# atmega32u4-breakout-v3.net
KiCad netlist of a schematic drawn in EAGLE
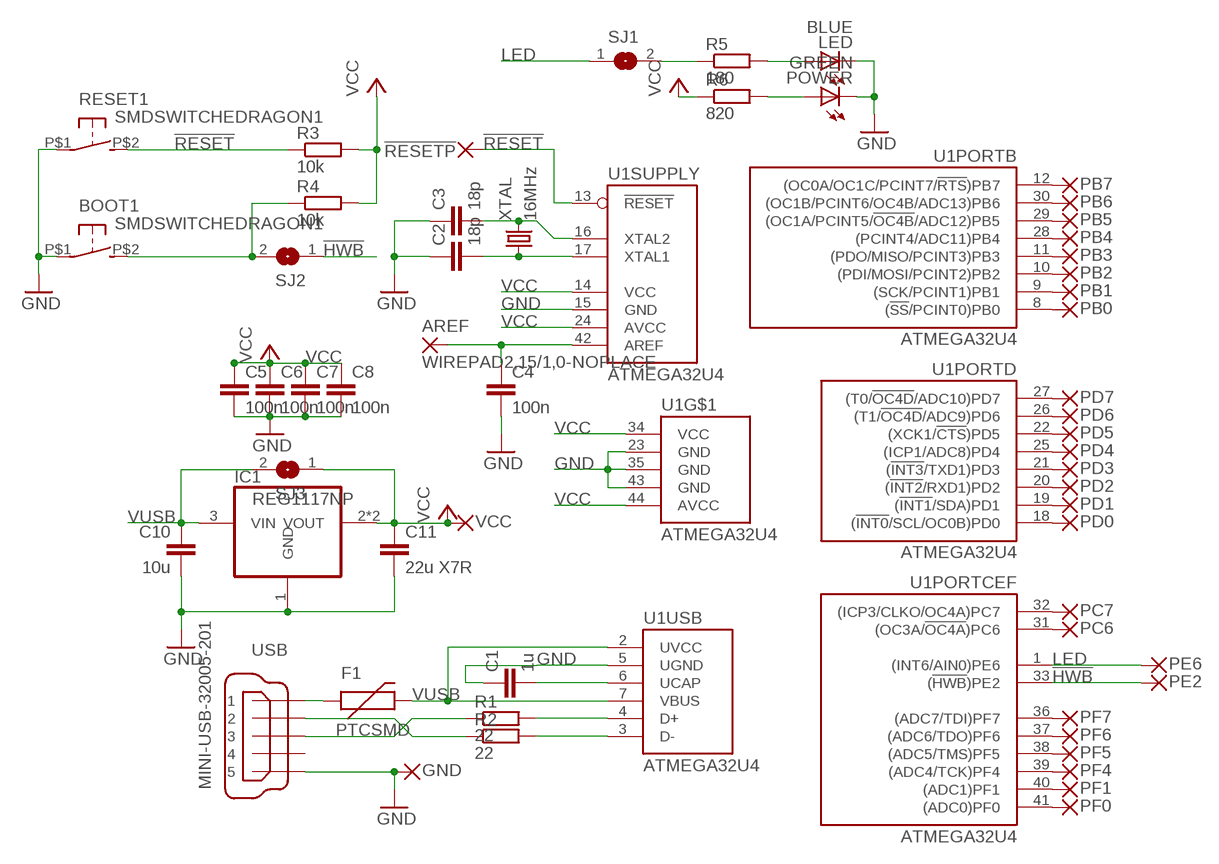
[diagram p0: schematic, sheet 1]

(export (version "E")
  (design (tool "Eeschema 10.0.6"))
  (components
    (comp (ref "!RESETP")
      (value "WIREPAD2,15/1,0-NOPLACE")
      (footprint "eagle-import:2,15_1,0-NOPLACE")
      (libsource (lib "eagle-import") (part "WIREPAD2,15/1,0-NOPLACE"))
    )
    (comp (ref "AREF")
      (value "WIREPAD2,15/1,0-NOPLACE")
      (footprint "eagle-import:2,15_1,0-NOPLACE")
      (libsource (lib "eagle-import") (part "WIREPAD2,15/1,0-NOPLACE"))
    )
    (comp (ref "BOOT1")
      (value "SMDSWITCHEDRAGON1")
      (footprint "eagle-import:EDRAGON1")
      (libsource (lib "eagle-import") (part "SMDSWITCHEDRAGON1"))
    )
    (comp (ref "C1")
      (value "1u")
      (footprint "eagle-import:C0603")
      (libsource (lib "eagle-import") (part "C-EUC0603"))
    )
    (comp (ref "C2")
      (value "18p")
      (footprint "eagle-import:C0603")
      (libsource (lib "eagle-import") (part "C-EUC0603"))
    )
    (comp (ref "C3")
      (value "18p")
      (footprint "eagle-import:C0603")
      (libsource (lib "eagle-import") (part "C-EUC0603"))
    )
    (comp (ref "C4")
      (value "100n")
      (footprint "eagle-import:C0603")
      (libsource (lib "eagle-import") (part "C-EUC0603"))
    )
    (comp (ref "C5")
      (value "100n")
      (footprint "eagle-import:C0603")
      (libsource (lib "eagle-import") (part "C-EUC0603"))
    )
    (comp (ref "C6")
      (value "100n")
      (footprint "eagle-import:C0603")
      (libsource (lib "eagle-import") (part "C-EUC0603"))
    )
    (comp (ref "C7")
      (value "100n")
      (footprint "eagle-import:C0603")
      (libsource (lib "eagle-import") (part "C-EUC0603"))
    )
    (comp (ref "C8")
      (value "100n")
      (footprint "eagle-import:C0603")
      (libsource (lib "eagle-import") (part "C-EUC0603"))
    )
    (comp (ref "C10")
      (value "10u")
      (footprint "eagle-import:C0805K")
      (libsource (lib "eagle-import") (part "C-EUC0805K"))
    )
    (comp (ref "C11")
      (value "22u X7R")
      (footprint "eagle-import:C1206K")
      (libsource (lib "eagle-import") (part "C-EUC1206K"))
    )
    (comp (ref "F1")
      (value "PTCSMD")
      (footprint "eagle-import:PTC-1206")
      (libsource (lib "eagle-import") (part "PTCSMD"))
    )
    (comp (ref "GND")
      (value "WIREPAD2,15/1,0-NOPLACE")
      (footprint "eagle-import:2,15_1,0-NOPLACE")
      (libsource (lib "eagle-import") (part "WIREPAD2,15/1,0-NOPLACE"))
    )
    (comp (ref "IC1")
      (value "REG1117NP")
      (footprint "eagle-import:SOT223-NP")
      (libsource (lib "eagle-import") (part "REG1117NP"))
    )
    (comp (ref "LED")
      (value "BLUE")
      (footprint "eagle-import:CHIPLED_0805")
      (libsource (lib "eagle-import") (part "LEDCHIPLED_0805"))
    )
    (comp (ref "PB0")
      (value "WIREPAD2,15/1,0-NOPLACE")
      (footprint "eagle-import:2,15_1,0-NOPLACE")
      (libsource (lib "eagle-import") (part "WIREPAD2,15/1,0-NOPLACE"))
    )
    (comp (ref "PB1")
      (value "WIREPAD2,15/1,0-NOPLACE")
      (footprint "eagle-import:2,15_1,0-NOPLACE")
      (libsource (lib "eagle-import") (part "WIREPAD2,15/1,0-NOPLACE"))
    )
    (comp (ref "PB2")
      (value "WIREPAD2,15/1,0-NOPLACE")
      (footprint "eagle-import:2,15_1,0-NOPLACE")
      (libsource (lib "eagle-import") (part "WIREPAD2,15/1,0-NOPLACE"))
    )
    (comp (ref "PB3")
      (value "WIREPAD2,15/1,0-NOPLACE")
      (footprint "eagle-import:2,15_1,0-NOPLACE")
      (libsource (lib "eagle-import") (part "WIREPAD2,15/1,0-NOPLACE"))
    )
    (comp (ref "PB4")
      (value "WIREPAD2,15/1,0-NOPLACE")
      (footprint "eagle-import:2,15_1,0-NOPLACE")
      (libsource (lib "eagle-import") (part "WIREPAD2,15/1,0-NOPLACE"))
    )
    (comp (ref "PB5")
      (value "WIREPAD2,15/1,0-NOPLACE")
      (footprint "eagle-import:2,15_1,0-NOPLACE")
      (libsource (lib "eagle-import") (part "WIREPAD2,15/1,0-NOPLACE"))
    )
    (comp (ref "PB6")
      (value "WIREPAD2,15/1,0-NOPLACE")
      (footprint "eagle-import:2,15_1,0-NOPLACE")
      (libsource (lib "eagle-import") (part "WIREPAD2,15/1,0-NOPLACE"))
    )
    (comp (ref "PB7")
      (value "WIREPAD2,15/1,0-NOPLACE")
      (footprint "eagle-import:2,15_1,0-NOPLACE")
      (libsource (lib "eagle-import") (part "WIREPAD2,15/1,0-NOPLACE"))
    )
    (comp (ref "PC6")
      (value "WIREPAD2,15/1,0-NOPLACE")
      (footprint "eagle-import:2,15_1,0-NOPLACE")
      (libsource (lib "eagle-import") (part "WIREPAD2,15/1,0-NOPLACE"))
    )
    (comp (ref "PC7")
      (value "WIREPAD2,15/1,0-NOPLACE")
      (footprint "eagle-import:2,15_1,0-NOPLACE")
      (libsource (lib "eagle-import") (part "WIREPAD2,15/1,0-NOPLACE"))
    )
    (comp (ref "PD0")
      (value "WIREPAD2,15/1,0-NOPLACE")
      (footprint "eagle-import:2,15_1,0-NOPLACE")
      (libsource (lib "eagle-import") (part "WIREPAD2,15/1,0-NOPLACE"))
    )
    (comp (ref "PD1")
      (value "WIREPAD2,15/1,0-NOPLACE")
      (footprint "eagle-import:2,15_1,0-NOPLACE")
      (libsource (lib "eagle-import") (part "WIREPAD2,15/1,0-NOPLACE"))
    )
    (comp (ref "PD2")
      (value "WIREPAD2,15/1,0-NOPLACE")
      (footprint "eagle-import:2,15_1,0-NOPLACE")
      (libsource (lib "eagle-import") (part "WIREPAD2,15/1,0-NOPLACE"))
    )
    (comp (ref "PD3")
      (value "WIREPAD2,15/1,0-NOPLACE")
      (footprint "eagle-import:2,15_1,0-NOPLACE")
      (libsource (lib "eagle-import") (part "WIREPAD2,15/1,0-NOPLACE"))
    )
    (comp (ref "PD4")
      (value "WIREPAD2,15/1,0-NOPLACE")
      (footprint "eagle-import:2,15_1,0-NOPLACE")
      (libsource (lib "eagle-import") (part "WIREPAD2,15/1,0-NOPLACE"))
    )
    (comp (ref "PD5")
      (value "WIREPAD2,15/1,0-NOPLACE")
      (footprint "eagle-import:2,15_1,0-NOPLACE")
      (libsource (lib "eagle-import") (part "WIREPAD2,15/1,0-NOPLACE"))
    )
    (comp (ref "PD6")
      (value "WIREPAD2,15/1,0-NOPLACE")
      (footprint "eagle-import:2,15_1,0-NOPLACE")
      (libsource (lib "eagle-import") (part "WIREPAD2,15/1,0-NOPLACE"))
    )
    (comp (ref "PD7")
      (value "WIREPAD2,15/1,0-NOPLACE")
      (footprint "eagle-import:2,15_1,0-NOPLACE")
      (libsource (lib "eagle-import") (part "WIREPAD2,15/1,0-NOPLACE"))
    )
    (comp (ref "PE2")
      (value "WIREPAD2,15/1,0-NOPLACE")
      (footprint "eagle-import:2,15_1,0-NOPLACE")
      (libsource (lib "eagle-import") (part "WIREPAD2,15/1,0-NOPLACE"))
    )
    (comp (ref "PE6")
      (value "WIREPAD2,15/1,0-NOPLACE")
      (footprint "eagle-import:2,15_1,0-NOPLACE")
      (libsource (lib "eagle-import") (part "WIREPAD2,15/1,0-NOPLACE"))
    )
    (comp (ref "PF0")
      (value "WIREPAD2,15/1,0-NOPLACE")
      (footprint "eagle-import:2,15_1,0-NOPLACE")
      (libsource (lib "eagle-import") (part "WIREPAD2,15/1,0-NOPLACE"))
    )
    (comp (ref "PF1")
      (value "WIREPAD2,15/1,0-NOPLACE")
      (footprint "eagle-import:2,15_1,0-NOPLACE")
      (libsource (lib "eagle-import") (part "WIREPAD2,15/1,0-NOPLACE"))
    )
    (comp (ref "PF4")
      (value "WIREPAD2,15/1,0-NOPLACE")
      (footprint "eagle-import:2,15_1,0-NOPLACE")
      (libsource (lib "eagle-import") (part "WIREPAD2,15/1,0-NOPLACE"))
    )
    (comp (ref "PF5")
      (value "WIREPAD2,15/1,0-NOPLACE")
      (footprint "eagle-import:2,15_1,0-NOPLACE")
      (libsource (lib "eagle-import") (part "WIREPAD2,15/1,0-NOPLACE"))
    )
    (comp (ref "PF6")
      (value "WIREPAD2,15/1,0-NOPLACE")
      (footprint "eagle-import:2,15_1,0-NOPLACE")
      (libsource (lib "eagle-import") (part "WIREPAD2,15/1,0-NOPLACE"))
    )
    (comp (ref "PF7")
      (value "WIREPAD2,15/1,0-NOPLACE")
      (footprint "eagle-import:2,15_1,0-NOPLACE")
      (libsource (lib "eagle-import") (part "WIREPAD2,15/1,0-NOPLACE"))
    )
    (comp (ref "POWER")
      (value "GREEN")
      (footprint "eagle-import:CHIPLED_0805")
      (libsource (lib "eagle-import") (part "LEDCHIPLED_0805"))
    )
    (comp (ref "R1")
      (value "22")
      (footprint "eagle-import:R0603")
      (libsource (lib "eagle-import") (part "R-EU_R0603"))
    )
    (comp (ref "R2")
      (value "22")
      (footprint "eagle-import:R0603")
      (libsource (lib "eagle-import") (part "R-EU_R0603"))
    )
    (comp (ref "R3")
      (value "10k")
      (footprint "eagle-import:R0603")
      (libsource (lib "eagle-import") (part "R-EU_R0603"))
    )
    (comp (ref "R4")
      (value "10k")
      (footprint "eagle-import:R0603")
      (libsource (lib "eagle-import") (part "R-EU_R0603"))
    )
    (comp (ref "R5")
      (value "180")
      (footprint "eagle-import:R0603")
      (libsource (lib "eagle-import") (part "R-EU_R0603"))
    )
    (comp (ref "R6")
      (value "820")
      (footprint "eagle-import:R0603")
      (libsource (lib "eagle-import") (part "R-EU_R0603"))
    )
    (comp (ref "RESET1")
      (value "SMDSWITCHEDRAGON1")
      (footprint "eagle-import:EDRAGON1")
      (libsource (lib "eagle-import") (part "SMDSWITCHEDRAGON1"))
    )
    (comp (ref "SJ1") (value "SJ") (footprint "eagle-import:SJ") (libsource (lib "eagle-import") (part "SJ")))
    (comp (ref "SJ2") (value "SJ") (footprint "eagle-import:SJ") (libsource (lib "eagle-import") (part "SJ")))
    (comp (ref "SJ3")
      (value "SJNP")
      (footprint "eagle-import:SJNP")
      (libsource (lib "eagle-import") (part "SJNP"))
    )
    (comp (ref "U1")
      (value "ATMEGA32U4")
      (footprint "eagle-import:TQFP44")
      (libsource (lib "eagle-import") (part "ATMEGAXU4TQFP44"))
    )
    (comp (ref "USB")
      (value "MINI-USB-32005-201")
      (footprint "eagle-import:32005-201")
      (libsource (lib "eagle-import") (part "MINI-USB-32005-201"))
    )
    (comp (ref "VCC")
      (value "WIREPAD2,15/1,0-NOPLACE")
      (footprint "eagle-import:2,15_1,0-NOPLACE")
      (libsource (lib "eagle-import") (part "WIREPAD2,15/1,0-NOPLACE"))
    )
    (comp (ref "XTAL")
      (value "16MHz")
      (footprint "eagle-import:ABM7")
      (libsource (lib "eagle-import") (part "CRYSTALABM7"))
    )
  )
  (nets
    (net (code "1") (name "/LED") (class "Default")
      (node (ref "PE6") (pin "1") (pinfunction "P_1") (pintype "passive"))
      (node (ref "SJ1") (pin "1") (pinfunction "1_1") (pintype "passive"))
      (node (ref "U1") (pin "1") (pinfunction "(INT6/AIN0)PE6_1") (pintype "bidirectional"))
    )
    (net (code "2") (name "/VUSB") (class "Default")
      (node (ref "C10") (pin "1") (pinfunction "1_1") (pintype "passive"))
      (node (ref "F1") (pin "2") (pinfunction "2_2") (pintype "bidirectional"))
      (node (ref "IC1") (pin "3") (pinfunction "VIN_3") (pintype "input"))
      (node (ref "SJ3") (pin "2") (pinfunction "2_2") (pintype "passive"))
      (node (ref "U1") (pin "2") (pinfunction "UVCC_2") (pintype "power_in"))
      (node (ref "U1") (pin "7") (pinfunction "VBUS_7") (pintype "power_in"))
    )
    (net (code "3") (name "/~{HWB}") (class "Default")
      (node (ref "PE2") (pin "1") (pinfunction "P_1") (pintype "passive"))
      (node (ref "SJ2") (pin "1") (pinfunction "1_1") (pintype "passive"))
      (node (ref "U1") (pin "33") (pinfunction "(~{HWB})PE2_33") (pintype "bidirectional"))
    )
    (net (code "4") (name "/~{RESET}") (class "Default")
      (node (ref "!RESETP") (pin "1") (pinfunction "P_1") (pintype "passive"))
      (node (ref "R3") (pin "1") (pinfunction "1_1") (pintype "passive"))
      (node (ref "RESET1") (pin "P$2") (pinfunction "S_P$2") (pintype "passive"))
      (node (ref "U1") (pin "13") (pinfunction "~{RESET}_13") (pintype "input"))
    )
    (net (code "5") (name "GND") (class "Default")
      (node (ref "BOOT1") (pin "P$1") (pinfunction "P_P$1") (pintype "passive"))
      (node (ref "C1") (pin "1") (pinfunction "1_1") (pintype "passive"))
      (node (ref "C10") (pin "2") (pinfunction "2_2") (pintype "passive"))
      (node (ref "C11") (pin "2") (pinfunction "2_2") (pintype "passive"))
      (node (ref "C2") (pin "1") (pinfunction "1_1") (pintype "passive"))
      (node (ref "C3") (pin "1") (pinfunction "1_1") (pintype "passive"))
      (node (ref "C4") (pin "2") (pinfunction "2_2") (pintype "passive"))
      (node (ref "C5") (pin "2") (pinfunction "2_2") (pintype "passive"))
      (node (ref "C6") (pin "2") (pinfunction "2_2") (pintype "passive"))
      (node (ref "C7") (pin "2") (pinfunction "2_2") (pintype "passive"))
      (node (ref "C8") (pin "2") (pinfunction "2_2") (pintype "passive"))
      (node (ref "GND") (pin "1") (pinfunction "P_1") (pintype "passive"))
      (node (ref "IC1") (pin "1") (pinfunction "GND_1") (pintype "power_in"))
      (node (ref "LED") (pin "C") (pinfunction "C_C") (pintype "passive"))
      (node (ref "POWER") (pin "C") (pinfunction "C_C") (pintype "passive"))
      (node (ref "RESET1") (pin "P$1") (pinfunction "P_P$1") (pintype "passive"))
      (node (ref "U1") (pin "15") (pinfunction "GND_15") (pintype "power_in"))
      (node (ref "U1") (pin "23") (pinfunction "GND_23") (pintype "power_in"))
      (node (ref "U1") (pin "35") (pinfunction "GND_35") (pintype "power_in"))
      (node (ref "U1") (pin "43") (pinfunction "GND_43") (pintype "power_in"))
      (node (ref "U1") (pin "5") (pinfunction "UGND_5") (pintype "power_in"))
      (node (ref "USB") (pin "5") (pinfunction "5_5") (pintype "passive"))
    )
    (net (code "6") (name "Net-(AREF-P)") (class "Default")
      (node (ref "AREF") (pin "1") (pinfunction "P_1") (pintype "passive"))
      (node (ref "C4") (pin "1") (pinfunction "1_1") (pintype "passive"))
      (node (ref "U1") (pin "42") (pinfunction "AREF_42") (pintype "power_in"))
    )
    (net (code "7") (name "Net-(BOOT1-S)") (class "Default")
      (node (ref "BOOT1") (pin "P$2") (pinfunction "S_P$2") (pintype "passive"))
      (node (ref "R4") (pin "1") (pinfunction "1_1") (pintype "passive"))
      (node (ref "SJ2") (pin "2") (pinfunction "2_2") (pintype "passive"))
    )
    (net (code "8") (name "Net-(F1-Pad1)") (class "Default")
      (node (ref "F1") (pin "1") (pinfunction "1_1") (pintype "bidirectional"))
      (node (ref "USB") (pin "1") (pinfunction "1_1") (pintype "passive"))
    )
    (net (code "9") (name "Net-(LED-PadA)") (class "Default")
      (node (ref "LED") (pin "A") (pinfunction "A_A") (pintype "passive"))
      (node (ref "R5") (pin "2") (pinfunction "2_2") (pintype "passive"))
    )
    (net (code "10") (name "Net-(PB0-P)") (class "Default")
      (node (ref "PB0") (pin "1") (pinfunction "P_1") (pintype "passive"))
      (node (ref "U1") (pin "8") (pinfunction "(~{SS}/PCINT0)PB0_8") (pintype "bidirectional"))
    )
    (net (code "11") (name "Net-(PB1-P)") (class "Default")
      (node (ref "PB1") (pin "1") (pinfunction "P_1") (pintype "passive"))
      (node (ref "U1") (pin "9") (pinfunction "(SCK/PCINT1)PB1_9") (pintype "bidirectional"))
    )
    (net (code "12") (name "Net-(PB2-P)") (class "Default")
      (node (ref "PB2") (pin "1") (pinfunction "P_1") (pintype "passive"))
      (node (ref "U1") (pin "10") (pinfunction "(PDI/MOSI/PCINT2)PB2_10") (pintype "bidirectional"))
    )
    (net (code "13") (name "Net-(PB3-P)") (class "Default")
      (node (ref "PB3") (pin "1") (pinfunction "P_1") (pintype "passive"))
      (node (ref "U1") (pin "11") (pinfunction "(PDO/MISO/PCINT3)PB3_11") (pintype "bidirectional"))
    )
    (net (code "14") (name "Net-(PB4-P)") (class "Default")
      (node (ref "PB4") (pin "1") (pinfunction "P_1") (pintype "passive"))
      (node (ref "U1") (pin "28") (pinfunction "(PCINT4/ADC11)PB4_28") (pintype "bidirectional"))
    )
    (net (code "15") (name "Net-(PB5-P)") (class "Default")
      (node (ref "PB5") (pin "1") (pinfunction "P_1") (pintype "passive"))
      (node (ref "U1") (pin "29") (pinfunction "(OC1A/PCINT5/~{OC4B}/ADC12)PB5_29") (pintype "bidirectional"))
    )
    (net (code "16") (name "Net-(PB6-P)") (class "Default")
      (node (ref "PB6") (pin "1") (pinfunction "P_1") (pintype "passive"))
      (node (ref "U1") (pin "30") (pinfunction "(OC1B/PCINT6/OC4B/ADC13)PB6_30") (pintype "bidirectional"))
    )
    (net (code "17") (name "Net-(PB7-P)") (class "Default")
      (node (ref "PB7") (pin "1") (pinfunction "P_1") (pintype "passive"))
      (node (ref "U1") (pin "12") (pinfunction "(OC0A/OC1C/PCINT7/~{RTS})PB7_12") (pintype "bidirectional"))
    )
    (net (code "18") (name "Net-(PC6-P)") (class "Default")
      (node (ref "PC6") (pin "1") (pinfunction "P_1") (pintype "passive"))
      (node (ref "U1") (pin "31") (pinfunction "(OC3A/~{OC4A})PC6_31") (pintype "bidirectional"))
    )
    (net (code "19") (name "Net-(PC7-P)") (class "Default")
      (node (ref "PC7") (pin "1") (pinfunction "P_1") (pintype "passive"))
      (node (ref "U1") (pin "32") (pinfunction "(ICP3/CLKO/OC4A)PC7_32") (pintype "bidirectional"))
    )
    (net (code "20") (name "Net-(PD0-P)") (class "Default")
      (node (ref "PD0") (pin "1") (pinfunction "P_1") (pintype "passive"))
      (node (ref "U1") (pin "18") (pinfunction "(~{INT0}/SCL/OC0B)PD0_18") (pintype "bidirectional"))
    )
    (net (code "21") (name "Net-(PD1-P)") (class "Default")
      (node (ref "PD1") (pin "1") (pinfunction "P_1") (pintype "passive"))
      (node (ref "U1") (pin "19") (pinfunction "(~{INT1}/SDA)PD1_19") (pintype "bidirectional"))
    )
    (net (code "22") (name "Net-(PD2-P)") (class "Default")
      (node (ref "PD2") (pin "1") (pinfunction "P_1") (pintype "passive"))
      (node (ref "U1") (pin "20") (pinfunction "(~{INT2}/RXD1)PD2_20") (pintype "bidirectional"))
    )
    (net (code "23") (name "Net-(PD3-P)") (class "Default")
      (node (ref "PD3") (pin "1") (pinfunction "P_1") (pintype "passive"))
      (node (ref "U1") (pin "21") (pinfunction "(~{INT3}/TXD1)PD3_21") (pintype "bidirectional"))
    )
    (net (code "24") (name "Net-(PD4-P)") (class "Default")
      (node (ref "PD4") (pin "1") (pinfunction "P_1") (pintype "passive"))
      (node (ref "U1") (pin "25") (pinfunction "(ICP1/ADC8)PD4_25") (pintype "bidirectional"))
    )
    (net (code "25") (name "Net-(PD5-P)") (class "Default")
      (node (ref "PD5") (pin "1") (pinfunction "P_1") (pintype "passive"))
      (node (ref "U1") (pin "22") (pinfunction "(XCK1/~{CTS})PD5_22") (pintype "bidirectional"))
    )
    (net (code "26") (name "Net-(PD6-P)") (class "Default")
      (node (ref "PD6") (pin "1") (pinfunction "P_1") (pintype "passive"))
      (node (ref "U1") (pin "26") (pinfunction "(T1/~{OC4D}/ADC9)PD6_26") (pintype "bidirectional"))
    )
    (net (code "27") (name "Net-(PD7-P)") (class "Default")
      (node (ref "PD7") (pin "1") (pinfunction "P_1") (pintype "passive"))
      (node (ref "U1") (pin "27") (pinfunction "(T0/~{OC4D}/ADC10)PD7_27") (pintype "bidirectional"))
    )
    (net (code "28") (name "Net-(PF0-P)") (class "Default")
      (node (ref "PF0") (pin "1") (pinfunction "P_1") (pintype "passive"))
      (node (ref "U1") (pin "41") (pinfunction "(ADC0)PF0_41") (pintype "bidirectional"))
    )
    (net (code "29") (name "Net-(PF1-P)") (class "Default")
      (node (ref "PF1") (pin "1") (pinfunction "P_1") (pintype "passive"))
      (node (ref "U1") (pin "40") (pinfunction "(ADC1)PF1_40") (pintype "bidirectional"))
    )
    (net (code "30") (name "Net-(PF4-P)") (class "Default")
      (node (ref "PF4") (pin "1") (pinfunction "P_1") (pintype "passive"))
      (node (ref "U1") (pin "39") (pinfunction "(ADC4/TCK)PF4_39") (pintype "bidirectional"))
    )
    (net (code "31") (name "Net-(PF5-P)") (class "Default")
      (node (ref "PF5") (pin "1") (pinfunction "P_1") (pintype "passive"))
      (node (ref "U1") (pin "38") (pinfunction "(ADC5/TMS)PF5_38") (pintype "bidirectional"))
    )
    (net (code "32") (name "Net-(PF6-P)") (class "Default")
      (node (ref "PF6") (pin "1") (pinfunction "P_1") (pintype "passive"))
      (node (ref "U1") (pin "37") (pinfunction "(ADC6/TDO)PF6_37") (pintype "bidirectional"))
    )
    (net (code "33") (name "Net-(PF7-P)") (class "Default")
      (node (ref "PF7") (pin "1") (pinfunction "P_1") (pintype "passive"))
      (node (ref "U1") (pin "36") (pinfunction "(ADC7/TDI)PF7_36") (pintype "bidirectional"))
    )
    (net (code "34") (name "Net-(POWER-PadA)") (class "Default")
      (node (ref "POWER") (pin "A") (pinfunction "A_A") (pintype "passive"))
      (node (ref "R6") (pin "2") (pinfunction "2_2") (pintype "passive"))
    )
    (net (code "35") (name "Net-(R1-Pad1)") (class "Default")
      (node (ref "R1") (pin "1") (pinfunction "1_1") (pintype "passive"))
      (node (ref "USB") (pin "3") (pinfunction "3_3") (pintype "passive"))
    )
    (net (code "36") (name "Net-(R2-Pad1)") (class "Default")
      (node (ref "R2") (pin "1") (pinfunction "1_1") (pintype "passive"))
      (node (ref "USB") (pin "2") (pinfunction "2_2") (pintype "passive"))
    )
    (net (code "37") (name "Net-(R5-Pad1)") (class "Default")
      (node (ref "R5") (pin "1") (pinfunction "1_1") (pintype "passive"))
      (node (ref "SJ1") (pin "2") (pinfunction "2_2") (pintype "passive"))
    )
    (net (code "38") (name "Net-(U1E-XTAL1)") (class "Default")
      (node (ref "C2") (pin "2") (pinfunction "2_2") (pintype "passive"))
      (node (ref "U1") (pin "17") (pinfunction "XTAL1_17") (pintype "bidirectional"))
      (node (ref "XTAL") (pin "P$1") (pinfunction "1_P$1") (pintype "passive"))
    )
    (net (code "39") (name "Net-(U1E-XTAL2)") (class "Default")
      (node (ref "C3") (pin "2") (pinfunction "2_2") (pintype "passive"))
      (node (ref "U1") (pin "16") (pinfunction "XTAL2_16") (pintype "bidirectional"))
      (node (ref "XTAL") (pin "P$2") (pinfunction "2_P$2") (pintype "passive"))
    )
    (net (code "40") (name "Net-(U1F-D+)") (class "Default")
      (node (ref "R1") (pin "2") (pinfunction "2_2") (pintype "passive"))
      (node (ref "U1") (pin "4") (pinfunction "D+_4") (pintype "bidirectional"))
    )
    (net (code "41") (name "Net-(U1F-D-)") (class "Default")
      (node (ref "R2") (pin "2") (pinfunction "2_2") (pintype "passive"))
      (node (ref "U1") (pin "3") (pinfunction "D-_3") (pintype "bidirectional"))
    )
    (net (code "42") (name "Net-(U1F-UCAP)") (class "Default")
      (node (ref "C1") (pin "2") (pinfunction "2_2") (pintype "passive"))
      (node (ref "U1") (pin "6") (pinfunction "UCAP_6") (pintype "power_in"))
    )
    (net (code "43") (name "VCC") (class "Default")
      (node (ref "C11") (pin "1") (pinfunction "1_1") (pintype "passive"))
      (node (ref "C5") (pin "1") (pinfunction "1_1") (pintype "passive"))
      (node (ref "C6") (pin "1") (pinfunction "1_1") (pintype "passive"))
      (node (ref "C7") (pin "1") (pinfunction "1_1") (pintype "passive"))
      (node (ref "C8") (pin "1") (pinfunction "1_1") (pintype "passive"))
      (node (ref "IC1") (pin "2") (pinfunction "VOUT_2") (pintype "output"))
      (node (ref "IC1") (pin "4") (pinfunction "VOUT_4") (pintype "output"))
      (node (ref "R3") (pin "2") (pinfunction "2_2") (pintype "passive"))
      (node (ref "R4") (pin "2") (pinfunction "2_2") (pintype "passive"))
      (node (ref "R6") (pin "1") (pinfunction "1_1") (pintype "passive"))
      (node (ref "SJ3") (pin "1") (pinfunction "1_1") (pintype "passive"))
      (node (ref "U1") (pin "14") (pinfunction "VCC_14") (pintype "power_in"))
      (node (ref "U1") (pin "24") (pinfunction "AVCC_24") (pintype "power_in"))
      (node (ref "U1") (pin "34") (pinfunction "VCC_34") (pintype "power_in"))
      (node (ref "U1") (pin "44") (pinfunction "AVCC_44") (pintype "power_in"))
      (node (ref "VCC") (pin "1") (pinfunction "P_1") (pintype "passive"))
    )
    (net (code "44") (name "unconnected-(USB-Pad4)") (class "Default")
      (node (ref "USB") (pin "4") (pinfunction "4_4") (pintype "passive"))
    )
  )
)
